# Decagon.net
KiCad netlist of a schematic drawn in EAGLE
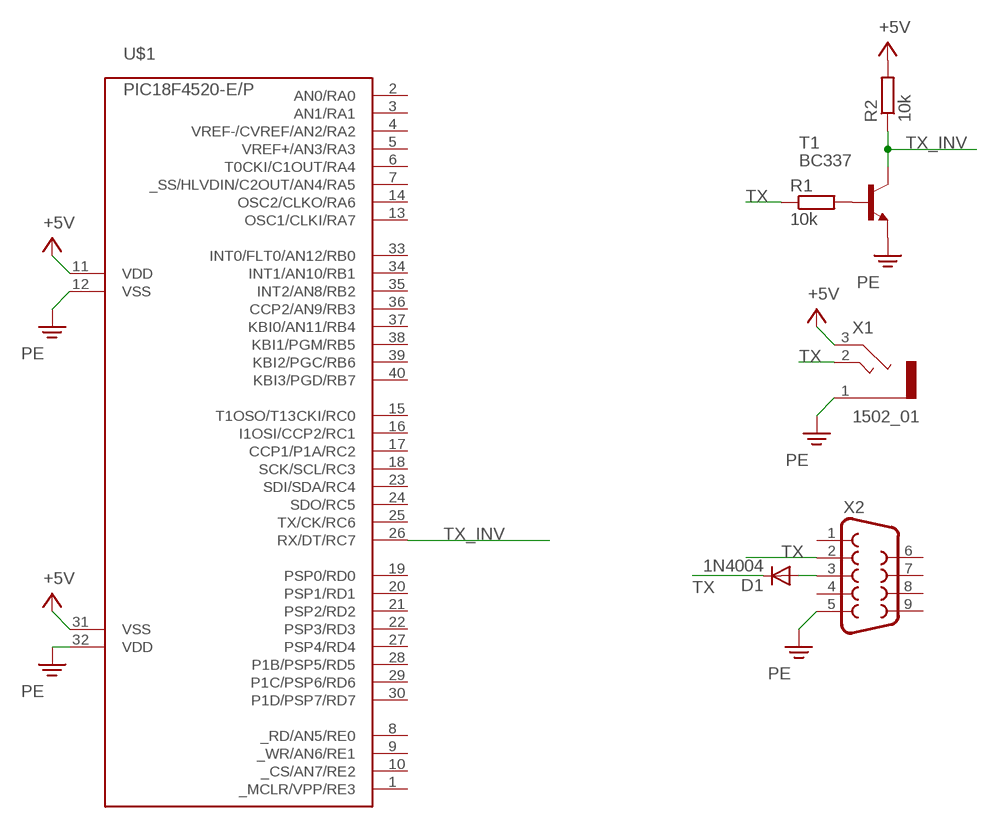
[diagram p0: schematic, sheet 1]

(export (version "E")
  (design (tool "Eeschema 10.0.6"))
  (components
    (comp (ref "D1")
      (value "1N4004")
      (footprint "eagle-import:DO41-10")
      (libsource (lib "eagle-import") (part "1N4004"))
    )
    (comp (ref "R1")
      (value "10k")
      (footprint "eagle-import:0207_10")
      (libsource (lib "eagle-import") (part "R-EU_0207/10"))
    )
    (comp (ref "R2")
      (value "10k")
      (footprint "eagle-import:0207_10")
      (libsource (lib "eagle-import") (part "R-EU_0207/10"))
    )
    (comp (ref "T1")
      (value "BC337")
      (footprint "eagle-import:TO92")
      (libsource (lib "eagle-import") (part "BC337"))
    )
    (comp (ref "U$1")
      (value "PIC18F4520-E/P")
      (footprint "eagle-import:DIL40")
      (libsource (lib "eagle-import") (part "PIC184520-E/PF"))
    )
    (comp (ref "X1")
      (value "1502_01")
      (footprint "eagle-import:1502_01")
      (libsource (lib "eagle-import") (part "1502_01"))
    )
    (comp (ref "X2")
      (value "F09VP")
      (footprint "eagle-import:F09VP")
      (libsource (lib "eagle-import") (part "F09VP"))
    )
  )
  (nets
    (net (code "1") (name "+5V") (class "Default")
      (node (ref "R2") (pin "2") (pinfunction "2_2") (pintype "passive"))
      (node (ref "U$1") (pin "11") (pinfunction "VDD_11") (pintype "power_in"))
      (node (ref "U$1") (pin "31") (pinfunction "VSS_31") (pintype "power_in"))
      (node (ref "X1") (pin "3") (pinfunction "2_3") (pintype "passive"))
    )
    (net (code "2") (name "/TX") (class "Default")
      (node (ref "D1") (pin "C") (pinfunction "C_C") (pintype "passive"))
      (node (ref "R1") (pin "1") (pinfunction "1_1") (pintype "passive"))
      (node (ref "X1") (pin "2") (pinfunction "3_2") (pintype "passive"))
      (node (ref "X2") (pin "2") (pinfunction "2_2") (pintype "passive"))
    )
    (net (code "3") (name "/TX_INV") (class "Default")
      (node (ref "R2") (pin "1") (pinfunction "1_1") (pintype "passive"))
      (node (ref "T1") (pin "3") (pinfunction "C_3") (pintype "passive"))
      (node (ref "U$1") (pin "26") (pinfunction "RX/DT/RC7_26") (pintype "bidirectional"))
    )
    (net (code "4") (name "Net-(D1-PadA)") (class "Default")
      (node (ref "D1") (pin "A") (pinfunction "A_A") (pintype "passive"))
      (node (ref "X2") (pin "3") (pinfunction "3_3") (pintype "passive"))
    )
    (net (code "5") (name "Net-(T1-B)") (class "Default")
      (node (ref "R1") (pin "2") (pinfunction "2_2") (pintype "passive"))
      (node (ref "T1") (pin "2") (pinfunction "B_2") (pintype "passive"))
    )
    (net (code "6") (name "PE") (class "Default")
      (node (ref "T1") (pin "1") (pinfunction "E_1") (pintype "passive"))
      (node (ref "U$1") (pin "12") (pinfunction "VSS_12") (pintype "power_in"))
      (node (ref "U$1") (pin "32") (pinfunction "VDD_32") (pintype "power_in"))
      (node (ref "X1") (pin "1") (pinfunction "1_1") (pintype "passive"))
      (node (ref "X2") (pin "5") (pinfunction "5_5") (pintype "passive"))
    )
    (net (code "7") (name "unconnected-(U$1-AN0{slash}RA0-Pad2)") (class "Default")
      (node (ref "U$1") (pin "2") (pinfunction "AN0/RA0_2") (pintype "bidirectional"))
    )
    (net (code "8") (name "unconnected-(U$1-AN1{slash}RA1-Pad3)") (class "Default")
      (node (ref "U$1") (pin "3") (pinfunction "AN1/RA1_3") (pintype "bidirectional"))
    )
    (net (code "9") (name "unconnected-(U$1-CCP1{slash}P1A{slash}RC2-Pad17)") (class "Default")
      (node (ref "U$1") (pin "17") (pinfunction "CCP1/P1A/RC2_17") (pintype "bidirectional"))
    )
    (net (code "10") (name "unconnected-(U$1-CCP2{slash}AN9{slash}RB3-Pad36)") (class "Default")
      (node (ref "U$1") (pin "36") (pinfunction "CCP2/AN9/RB3_36") (pintype "bidirectional"))
    )
    (net (code "11") (name "unconnected-(U$1-I1OSI{slash}CCP2{slash}RC1-Pad16)") (class "Default")
      (node (ref "U$1") (pin "16") (pinfunction "I1OSI/CCP2/RC1_16") (pintype "bidirectional"))
    )
    (net (code "12") (name "unconnected-(U$1-INT0{slash}FLT0{slash}AN12{slash}RB0-Pad33)") (class "Default")
      (node (ref "U$1") (pin "33") (pinfunction "INT0/FLT0/AN12/RB0_33") (pintype "bidirectional"))
    )
    (net (code "13") (name "unconnected-(U$1-INT1{slash}AN10{slash}RB1-Pad34)") (class "Default")
      (node (ref "U$1") (pin "34") (pinfunction "INT1/AN10/RB1_34") (pintype "bidirectional"))
    )
    (net (code "14") (name "unconnected-(U$1-INT2{slash}AN8{slash}RB2-Pad35)") (class "Default")
      (node (ref "U$1") (pin "35") (pinfunction "INT2/AN8/RB2_35") (pintype "bidirectional"))
    )
    (net (code "15") (name "unconnected-(U$1-KBI0{slash}AN11{slash}RB4-Pad37)") (class "Default")
      (node (ref "U$1") (pin "37") (pinfunction "KBI0/AN11/RB4_37") (pintype "bidirectional"))
    )
    (net (code "16") (name "unconnected-(U$1-KBI1{slash}PGM{slash}RB5-Pad38)") (class "Default")
      (node (ref "U$1") (pin "38") (pinfunction "KBI1/PGM/RB5_38") (pintype "bidirectional"))
    )
    (net (code "17") (name "unconnected-(U$1-KBI2{slash}PGC{slash}RB6-Pad39)") (class "Default")
      (node (ref "U$1") (pin "39") (pinfunction "KBI2/PGC/RB6_39") (pintype "bidirectional"))
    )
    (net (code "18") (name "unconnected-(U$1-KBI3{slash}PGD{slash}RB7-Pad40)") (class "Default")
      (node (ref "U$1") (pin "40") (pinfunction "KBI3/PGD/RB7_40") (pintype "bidirectional"))
    )
    (net (code "19") (name "unconnected-(U$1-OSC1{slash}CLKI{slash}RA7-Pad13)") (class "Default")
      (node (ref "U$1") (pin "13") (pinfunction "OSC1/CLKI/RA7_13") (pintype "bidirectional"))
    )
    (net (code "20") (name "unconnected-(U$1-OSC2{slash}CLKO{slash}RA6-Pad14)") (class "Default")
      (node (ref "U$1") (pin "14") (pinfunction "OSC2/CLKO/RA6_14") (pintype "bidirectional"))
    )
    (net (code "21") (name "unconnected-(U$1-P1B{slash}PSP5{slash}RD5-Pad28)") (class "Default")
      (node (ref "U$1") (pin "28") (pinfunction "P1B/PSP5/RD5_28") (pintype "bidirectional"))
    )
    (net (code "22") (name "unconnected-(U$1-P1C{slash}PSP6{slash}RD6-Pad29)") (class "Default")
      (node (ref "U$1") (pin "29") (pinfunction "P1C/PSP6/RD6_29") (pintype "bidirectional"))
    )
    (net (code "23") (name "unconnected-(U$1-P1D{slash}PSP7{slash}RD7-Pad30)") (class "Default")
      (node (ref "U$1") (pin "30") (pinfunction "P1D/PSP7/RD7_30") (pintype "bidirectional"))
    )
    (net (code "24") (name "unconnected-(U$1-PSP0{slash}RD0-Pad19)") (class "Default")
      (node (ref "U$1") (pin "19") (pinfunction "PSP0/RD0_19") (pintype "bidirectional"))
    )
    (net (code "25") (name "unconnected-(U$1-PSP1{slash}RD1-Pad20)") (class "Default")
      (node (ref "U$1") (pin "20") (pinfunction "PSP1/RD1_20") (pintype "bidirectional"))
    )
    (net (code "26") (name "unconnected-(U$1-PSP2{slash}RD2-Pad21)") (class "Default")
      (node (ref "U$1") (pin "21") (pinfunction "PSP2/RD2_21") (pintype "bidirectional"))
    )
    (net (code "27") (name "unconnected-(U$1-PSP3{slash}RD3-Pad22)") (class "Default")
      (node (ref "U$1") (pin "22") (pinfunction "PSP3/RD3_22") (pintype "bidirectional"))
    )
    (net (code "28") (name "unconnected-(U$1-PSP4{slash}RD4-Pad27)") (class "Default")
      (node (ref "U$1") (pin "27") (pinfunction "PSP4/RD4_27") (pintype "bidirectional"))
    )
    (net (code "29") (name "unconnected-(U$1-SCK{slash}SCL{slash}RC3-Pad18)") (class "Default")
      (node (ref "U$1") (pin "18") (pinfunction "SCK/SCL/RC3_18") (pintype "bidirectional"))
    )
    (net (code "30") (name "unconnected-(U$1-SDI{slash}SDA{slash}RC4-Pad23)") (class "Default")
      (node (ref "U$1") (pin "23") (pinfunction "SDI/SDA/RC4_23") (pintype "bidirectional"))
    )
    (net (code "31") (name "unconnected-(U$1-SDO{slash}RC5-Pad24)") (class "Default")
      (node (ref "U$1") (pin "24") (pinfunction "SDO/RC5_24") (pintype "bidirectional"))
    )
    (net (code "32") (name "unconnected-(U$1-T0CKI{slash}C1OUT{slash}RA4-Pad6)") (class "Default")
      (node (ref "U$1") (pin "6") (pinfunction "T0CKI/C1OUT/RA4_6") (pintype "bidirectional"))
    )
    (net (code "33") (name "unconnected-(U$1-T1OSO{slash}T13CKI{slash}RC0-Pad15)") (class "Default")
      (node (ref "U$1") (pin "15") (pinfunction "T1OSO/T13CKI/RC0_15") (pintype "bidirectional"))
    )
    (net (code "34") (name "unconnected-(U$1-TX{slash}CK{slash}RC6-Pad25)") (class "Default")
      (node (ref "U$1") (pin "25") (pinfunction "TX/CK/RC6_25") (pintype "bidirectional"))
    )
    (net (code "35") (name "unconnected-(U$1-VREF+{slash}AN3{slash}RA3-Pad5)") (class "Default")
      (node (ref "U$1") (pin "5") (pinfunction "VREF+/AN3/RA3_5") (pintype "bidirectional"))
    )
    (net (code "36") (name "unconnected-(U$1-VREF-{slash}CVREF{slash}AN2{slash}RA2-Pad4)") (class "Default")
      (node (ref "U$1") (pin "4") (pinfunction "VREF-/CVREF/AN2/RA2_4") (pintype "bidirectional"))
    )
    (net (code "37") (name "unconnected-(U$1-_CS{slash}AN7{slash}RE2-Pad10)") (class "Default")
      (node (ref "U$1") (pin "10") (pinfunction "_CS/AN7/RE2_10") (pintype "bidirectional"))
    )
    (net (code "38") (name "unconnected-(U$1-_MCLR{slash}VPP{slash}RE3-Pad1)") (class "Default")
      (node (ref "U$1") (pin "1") (pinfunction "_MCLR/VPP/RE3_1") (pintype "input"))
    )
    (net (code "39") (name "unconnected-(U$1-_RD{slash}AN5{slash}RE0-Pad8)") (class "Default")
      (node (ref "U$1") (pin "8") (pinfunction "_RD/AN5/RE0_8") (pintype "bidirectional"))
    )
    (net (code "40") (name "unconnected-(U$1-_SS{slash}HLVDIN{slash}C2OUT{slash}AN4{slash}RA5-Pad7)") (class "Default")
      (node (ref "U$1") (pin "7") (pinfunction "_SS/HLVDIN/C2OUT/AN4/RA5_7") (pintype "bidirectional"))
    )
    (net (code "41") (name "unconnected-(U$1-_WR{slash}AN6{slash}RE1-Pad9)") (class "Default")
      (node (ref "U$1") (pin "9") (pinfunction "_WR/AN6/RE1_9") (pintype "bidirectional"))
    )
    (net (code "42") (name "unconnected-(X2-Pad1)") (class "Default")
      (node (ref "X2") (pin "1") (pinfunction "1_1") (pintype "passive"))
    )
    (net (code "43") (name "unconnected-(X2-Pad4)") (class "Default")
      (node (ref "X2") (pin "4") (pinfunction "4_4") (pintype "passive"))
    )
    (net (code "44") (name "unconnected-(X2-Pad6)") (class "Default")
      (node (ref "X2") (pin "6") (pinfunction "6_6") (pintype "passive"))
    )
    (net (code "45") (name "unconnected-(X2-Pad7)") (class "Default")
      (node (ref "X2") (pin "7") (pinfunction "7_7") (pintype "passive"))
    )
    (net (code "46") (name "unconnected-(X2-Pad8)") (class "Default")
      (node (ref "X2") (pin "8") (pinfunction "8_8") (pintype "passive"))
    )
    (net (code "47") (name "unconnected-(X2-Pad9)") (class "Default")
      (node (ref "X2") (pin "9") (pinfunction "9_9") (pintype "passive"))
    )
  )
)
